# 9235HallEffectV1_0.net
KiCad netlist of a schematic drawn in EAGLE
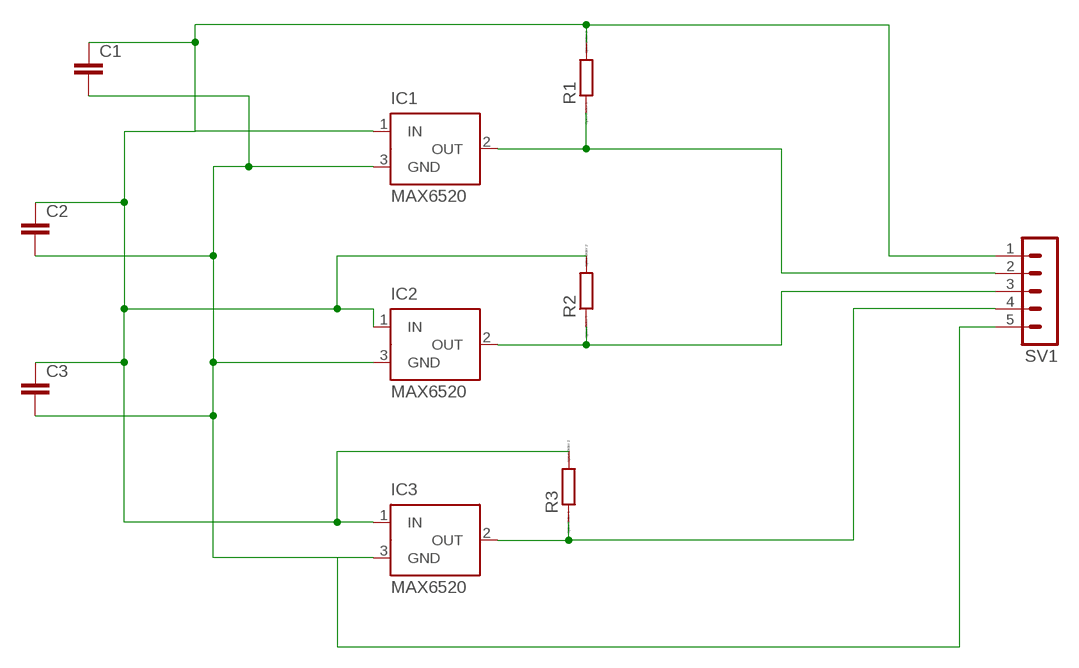
[diagram p0: schematic, sheet 1]

(export (version "E")
  (design (tool "Eeschema 10.0.6"))
  (components
    (comp (ref "C1")
      (value "C-EUC0603")
      (footprint "eagle-import:C0603")
      (libsource (lib "eagle-import") (part "C-EUC0603"))
    )
    (comp (ref "C2")
      (value "C-EUC0603")
      (footprint "eagle-import:C0603")
      (libsource (lib "eagle-import") (part "C-EUC0603"))
    )
    (comp (ref "C3")
      (value "C-EUC0603")
      (footprint "eagle-import:C0603")
      (libsource (lib "eagle-import") (part "C-EUC0603"))
    )
    (comp (ref "IC1")
      (value "MAX6520")
      (footprint "eagle-import:SOT23")
      (fields (field (name "MF") "MAXIM") (field (name "MPN") "MAX6520EUR-T"))
      (libsource (lib "eagle-import") (part "MAX6520"))
    )
    (comp (ref "IC2")
      (value "MAX6520")
      (footprint "eagle-import:SOT23")
      (fields (field (name "MF") "MAXIM") (field (name "MPN") "MAX6520EUR-T"))
      (libsource (lib "eagle-import") (part "MAX6520"))
    )
    (comp (ref "IC3")
      (value "MAX6520")
      (footprint "eagle-import:SOT23")
      (fields (field (name "MF") "MAXIM") (field (name "MPN") "MAX6520EUR-T"))
      (libsource (lib "eagle-import") (part "MAX6520"))
    )
    (comp (ref "R1")
      (value "RR0603")
      (footprint "eagle-import:R0603")
      (libsource (lib "eagle-import") (part "RR0603"))
    )
    (comp (ref "R2")
      (value "RR0603")
      (footprint "eagle-import:R0603")
      (libsource (lib "eagle-import") (part "RR0603"))
    )
    (comp (ref "R3")
      (value "RR0603")
      (footprint "eagle-import:R0603")
      (libsource (lib "eagle-import") (part "RR0603"))
    )
    (comp (ref "SV1")
      (value "MA05-1")
      (footprint "eagle-import:MA05-1")
      (libsource (lib "eagle-import") (part "MA05-1"))
    )
  )
  (nets
    (net (code "1") (name "Net-(IC1-GND)") (class "Default")
      (node (ref "C1") (pin "2") (pinfunction "2_2") (pintype "passive"))
      (node (ref "C2") (pin "2") (pinfunction "2_2") (pintype "passive"))
      (node (ref "C3") (pin "2") (pinfunction "2_2") (pintype "passive"))
      (node (ref "IC1") (pin "3") (pinfunction "GND_3") (pintype "power_in"))
      (node (ref "IC2") (pin "3") (pinfunction "GND_3") (pintype "power_in"))
      (node (ref "IC3") (pin "3") (pinfunction "GND_3") (pintype "power_in"))
      (node (ref "SV1") (pin "5") (pinfunction "5_5") (pintype "passive"))
    )
    (net (code "2") (name "Net-(IC1-IN)") (class "Default")
      (node (ref "C1") (pin "1") (pinfunction "1_1") (pintype "passive"))
      (node (ref "C2") (pin "1") (pinfunction "1_1") (pintype "passive"))
      (node (ref "C3") (pin "1") (pinfunction "1_1") (pintype "passive"))
      (node (ref "IC1") (pin "1") (pinfunction "IN_1") (pintype "input"))
      (node (ref "IC2") (pin "1") (pinfunction "IN_1") (pintype "input"))
      (node (ref "IC3") (pin "1") (pinfunction "IN_1") (pintype "input"))
      (node (ref "R1") (pin "2") (pinfunction "2_2") (pintype "passive"))
      (node (ref "R2") (pin "2") (pinfunction "2_2") (pintype "passive"))
      (node (ref "R3") (pin "2") (pinfunction "2_2") (pintype "passive"))
      (node (ref "SV1") (pin "1") (pinfunction "1_1") (pintype "passive"))
    )
    (net (code "3") (name "Net-(IC1-OUT)") (class "Default")
      (node (ref "IC1") (pin "2") (pinfunction "OUT_2") (pintype "output"))
      (node (ref "R1") (pin "1") (pinfunction "1_1") (pintype "passive"))
      (node (ref "SV1") (pin "2") (pinfunction "2_2") (pintype "passive"))
    )
    (net (code "4") (name "Net-(IC2-OUT)") (class "Default")
      (node (ref "IC2") (pin "2") (pinfunction "OUT_2") (pintype "output"))
      (node (ref "R2") (pin "1") (pinfunction "1_1") (pintype "passive"))
      (node (ref "SV1") (pin "3") (pinfunction "3_3") (pintype "passive"))
    )
    (net (code "5") (name "Net-(IC3-OUT)") (class "Default")
      (node (ref "IC3") (pin "2") (pinfunction "OUT_2") (pintype "output"))
      (node (ref "R3") (pin "1") (pinfunction "1_1") (pintype "passive"))
      (node (ref "SV1") (pin "4") (pinfunction "4_4") (pintype "passive"))
    )
  )
)
